# IR_Receiver.net
KiCad netlist of a schematic drawn in EAGLE
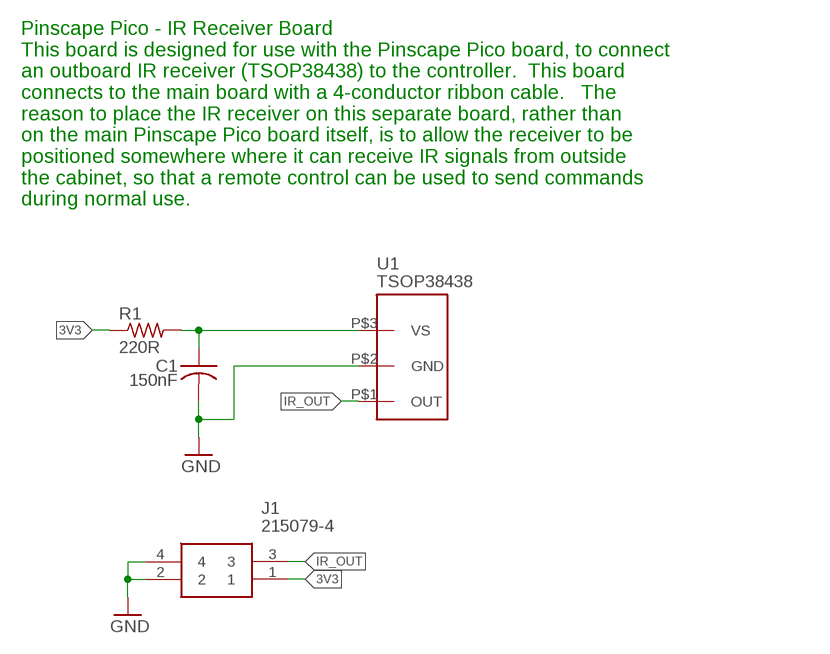
[diagram p0: schematic, sheet 1]

(export (version "E")
  (design (tool "Eeschema 10.0.6"))
  (components
    (comp (ref "C1")
      (value "150nF")
      (footprint "eagle-import:C1206")
      (libsource (lib "eagle-import") (part "C-USC1206"))
    )
    (comp (ref "J1")
      (value "215079-4")
      (footprint "eagle-import:2150794")
      (fields (field (name "MOUSER_PART_NUMBER") "571-215079-4"))
      (libsource (lib "eagle-import") (part "215079-4"))
    )
    (comp (ref "R1")
      (value "220R")
      (footprint "eagle-import:R1206")
      (fields (field (name "PARTNO") "660-MS1/4DCT52R1002"))
      (libsource (lib "eagle-import") (part "R-US_R1206"))
    )
    (comp (ref "U1")
      (value "TSOP38438")
      (footprint "eagle-import:TSOP382")
      (libsource (lib "eagle-import") (part "TSOP382"))
    )
  )
  (nets
    (net (code "1") (name "3V3") (class "Default")
      (node (ref "J1") (pin "1") (pinfunction "1_1") (pintype "bidirectional"))
      (node (ref "R1") (pin "1") (pinfunction "1_1") (pintype "passive"))
    )
    (net (code "2") (name "GND") (class "Default")
      (node (ref "C1") (pin "2") (pinfunction "2_2") (pintype "passive"))
      (node (ref "J1") (pin "2") (pinfunction "2_2") (pintype "bidirectional"))
      (node (ref "J1") (pin "4") (pinfunction "4_4") (pintype "bidirectional"))
      (node (ref "U1") (pin "P$2") (pinfunction "GND_P$2") (pintype "power_in"))
    )
    (net (code "3") (name "IR_OUT") (class "Default")
      (node (ref "J1") (pin "3") (pinfunction "3_3") (pintype "bidirectional"))
      (node (ref "U1") (pin "P$1") (pinfunction "OUT_P$1") (pintype "output"))
    )
    (net (code "4") (name "Net-(U1-VS)") (class "Default")
      (node (ref "C1") (pin "1") (pinfunction "1_1") (pintype "passive"))
      (node (ref "R1") (pin "2") (pinfunction "2_2") (pintype "passive"))
      (node (ref "U1") (pin "P$3") (pinfunction "VS_P$3") (pintype "power_in"))
    )
  )
)
